# RP2040-Shim-2.net
KiCad netlist of a schematic drawn in EAGLE
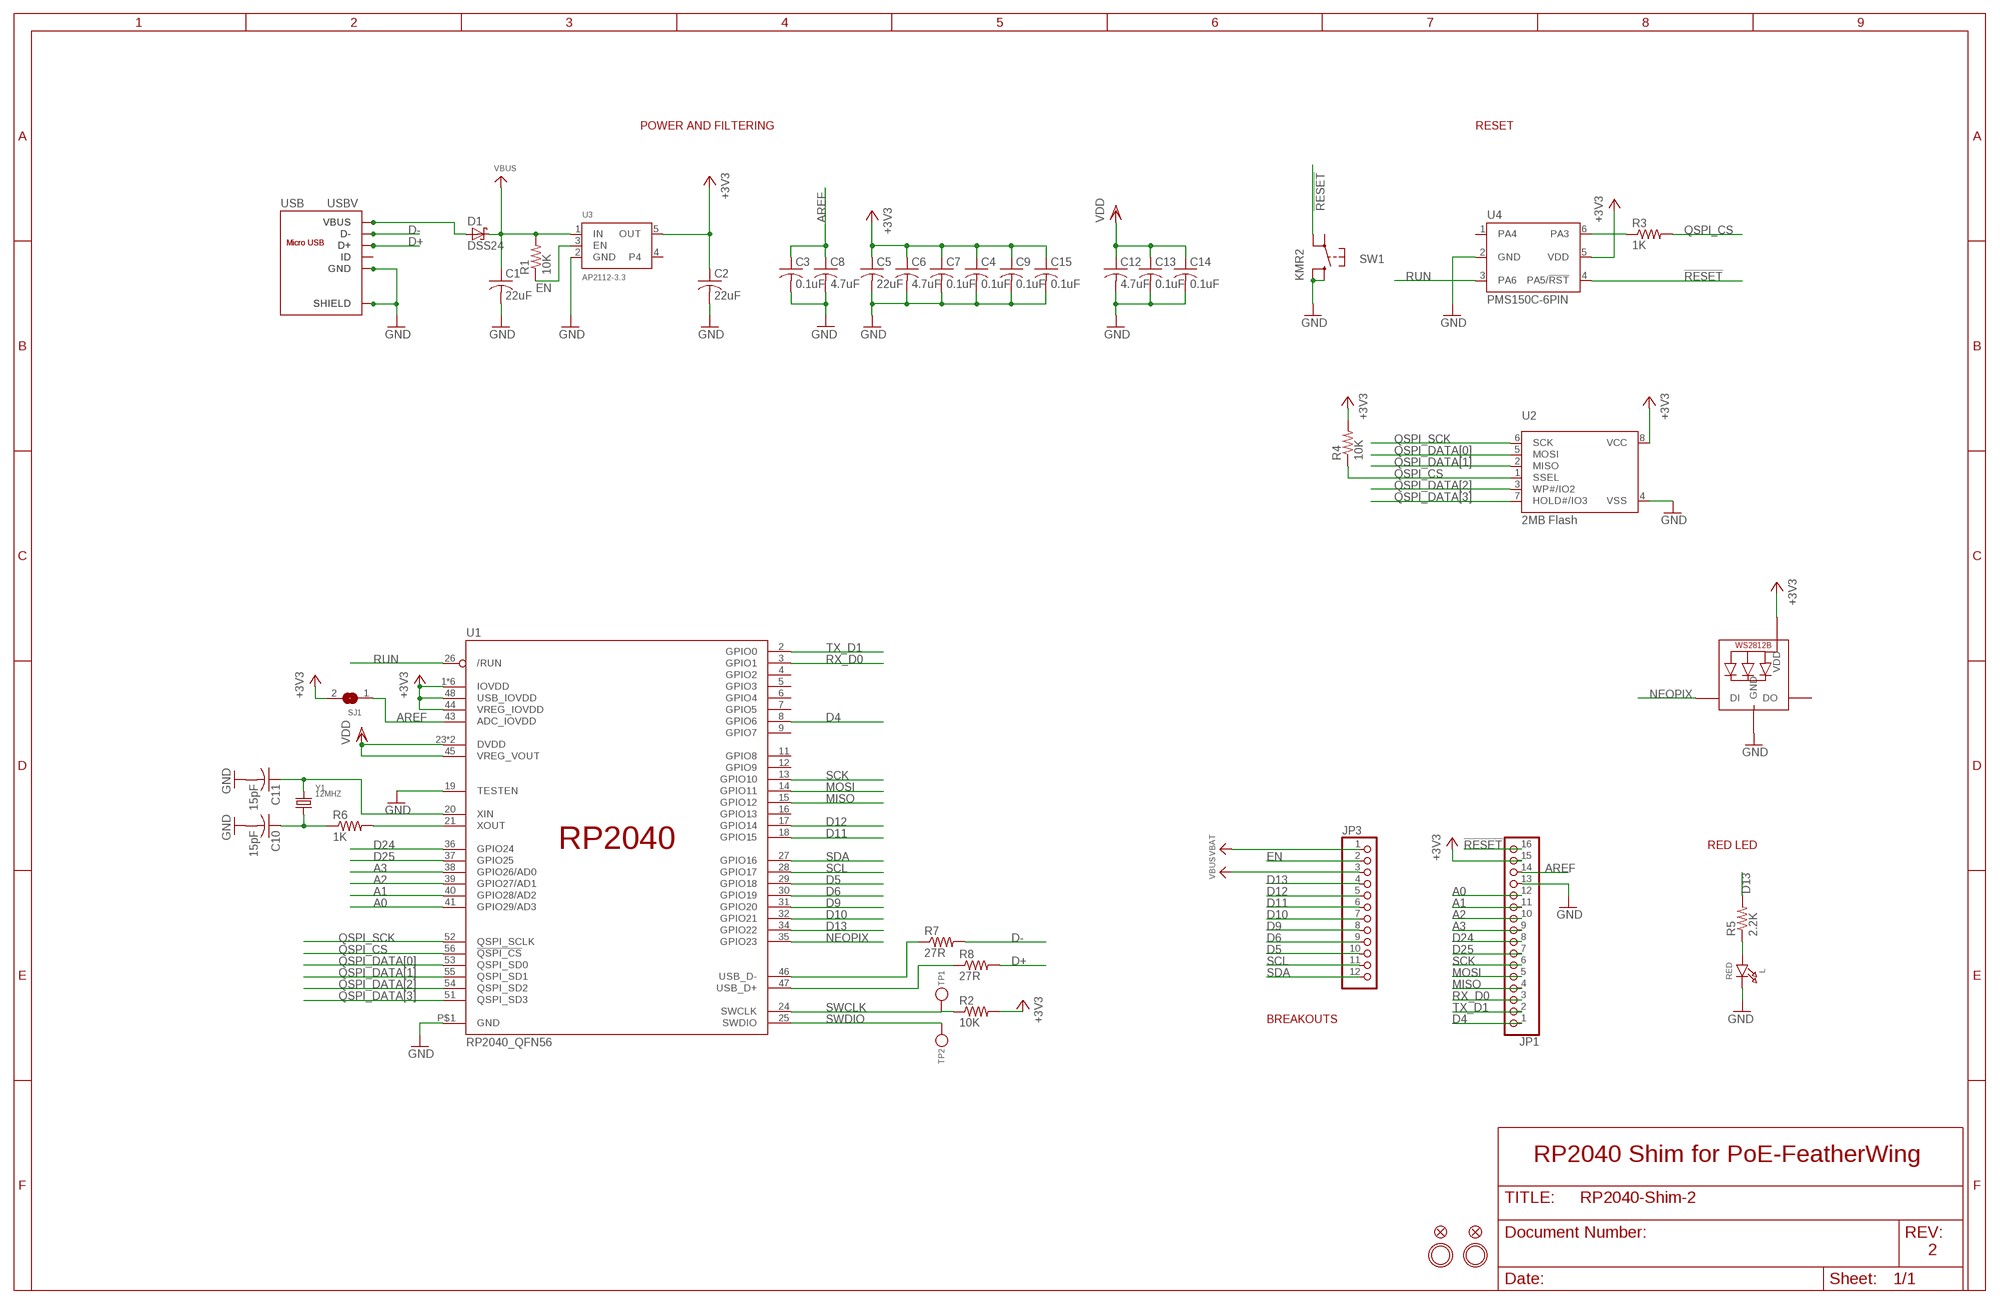
[diagram p0: schematic, sheet 1]

(export (version "E")
  (design (tool "Eeschema 10.0.6"))
  (components
    (comp (ref "C1")
      (value "22uF")
      (footprint "eagle-import:C0805K")
      (libsource (lib "eagle-import") (part "C-USC0805K"))
    )
    (comp (ref "C2")
      (value "22uF")
      (footprint "eagle-import:C0805K")
      (libsource (lib "eagle-import") (part "C-USC0805K"))
    )
    (comp (ref "C3")
      (value "0.1uF")
      (footprint "eagle-import:C0402K")
      (libsource (lib "eagle-import") (part "C-USC0402K"))
    )
    (comp (ref "C4")
      (value "0.1uF")
      (footprint "eagle-import:C0402K")
      (libsource (lib "eagle-import") (part "C-USC0402K"))
    )
    (comp (ref "C5")
      (value "22uF")
      (footprint "eagle-import:C0805K")
      (libsource (lib "eagle-import") (part "C-USC0805K"))
    )
    (comp (ref "C6")
      (value "4.7uF")
      (footprint "eagle-import:C0402K")
      (libsource (lib "eagle-import") (part "C-USC0402K"))
    )
    (comp (ref "C7")
      (value "0.1uF")
      (footprint "eagle-import:C0402K")
      (libsource (lib "eagle-import") (part "C-USC0402K"))
    )
    (comp (ref "C8")
      (value "4.7uF")
      (footprint "eagle-import:C0402K")
      (libsource (lib "eagle-import") (part "C-USC0402K"))
    )
    (comp (ref "C9")
      (value "0.1uF")
      (footprint "eagle-import:C0402K")
      (libsource (lib "eagle-import") (part "C-USC0402K"))
    )
    (comp (ref "C10")
      (value "15pF")
      (footprint "eagle-import:C0402K")
      (libsource (lib "eagle-import") (part "C-USC0402K"))
    )
    (comp (ref "C11")
      (value "15pF")
      (footprint "eagle-import:C0402K")
      (libsource (lib "eagle-import") (part "C-USC0402K"))
    )
    (comp (ref "C12")
      (value "4.7uF")
      (footprint "eagle-import:C0402K")
      (libsource (lib "eagle-import") (part "C-USC0402K"))
    )
    (comp (ref "C13")
      (value "0.1uF")
      (footprint "eagle-import:C0402K")
      (libsource (lib "eagle-import") (part "C-USC0402K"))
    )
    (comp (ref "C14")
      (value "0.1uF")
      (footprint "eagle-import:C0402K")
      (libsource (lib "eagle-import") (part "C-USC0402K"))
    )
    (comp (ref "C15")
      (value "0.1uF")
      (footprint "eagle-import:C0402K")
      (libsource (lib "eagle-import") (part "C-USC0402K"))
    )
    (comp (ref "D1")
      (value "DSS24")
      (footprint "eagle-import:SOD123FL")
      (libsource (lib "eagle-import") (part "DSS24"))
    )
    (comp (ref "JP1")
      (value "HEADER-1X16ROUND")
      (footprint "eagle-import:1X16_ROUND")
      (libsource (lib "eagle-import") (part "HEADER-1X16ROUND"))
    )
    (comp (ref "JP3")
      (value "HEADER-1X12")
      (footprint "eagle-import:1X12_ROUND")
      (libsource (lib "eagle-import") (part "HEADER-1X12"))
    )
    (comp (ref "L")
      (value "RED")
      (footprint "eagle-import:CHIPLED_0805_NOOUTLINE")
      (libsource (lib "eagle-import") (part "LED0805_NOOUTLINE"))
    )
    (comp (ref "LED1")
      (value "WS2812B3535")
      (footprint "eagle-import:LED3535")
      (libsource (lib "eagle-import") (part "WS2812B3535"))
    )
    (comp (ref "R1")
      (value "10K")
      (footprint "eagle-import:R0402")
      (libsource (lib "eagle-import") (part "R-US_R0402"))
    )
    (comp (ref "R2")
      (value "10K")
      (footprint "eagle-import:R0402")
      (libsource (lib "eagle-import") (part "R-US_R0402"))
    )
    (comp (ref "R3")
      (value "1K")
      (footprint "eagle-import:R0402")
      (libsource (lib "eagle-import") (part "R-US_R0402"))
    )
    (comp (ref "R4")
      (value "10K")
      (footprint "eagle-import:R0402")
      (libsource (lib "eagle-import") (part "R-US_R0402"))
    )
    (comp (ref "R5")
      (value "2.2K")
      (footprint "eagle-import:R0402")
      (libsource (lib "eagle-import") (part "R-US_R0402"))
    )
    (comp (ref "R6")
      (value "1K")
      (footprint "eagle-import:R0402")
      (libsource (lib "eagle-import") (part "R-US_R0402"))
    )
    (comp (ref "R7")
      (value "27R")
      (footprint "eagle-import:R0402")
      (libsource (lib "eagle-import") (part "R-US_R0402"))
    )
    (comp (ref "R8")
      (value "27R")
      (footprint "eagle-import:R0402")
      (libsource (lib "eagle-import") (part "R-US_R0402"))
    )
    (comp (ref "SJ1")
      (value "SOLDERJUMPERCLOSED")
      (footprint "eagle-import:SOLDERJUMPER_CLOSEDWIRE")
      (libsource (lib "eagle-import") (part "SOLDERJUMPERCLOSED"))
    )
    (comp (ref "SW1")
      (value "KMR2")
      (footprint "eagle-import:BTN_KMR2_4.6X2.8")
      (libsource (lib "eagle-import") (part "SWITCH_TACT_SMT4.6X2.8"))
    )
    (comp (ref "TP1")
      (value "TESTPOINTROUND1.5MM")
      (footprint "eagle-import:TESTPOINT_ROUND_1.5MM")
      (libsource (lib "eagle-import") (part "TESTPOINTROUND1.5MM"))
    )
    (comp (ref "TP2")
      (value "TESTPOINTROUND1.5MM")
      (footprint "eagle-import:TESTPOINT_ROUND_1.5MM")
      (libsource (lib "eagle-import") (part "TESTPOINTROUND1.5MM"))
    )
    (comp (ref "U$31")
      (value "MOUNTINGHOLE2.5")
      (footprint "eagle-import:MOUNTINGHOLE_2.5_PLATED")
      (libsource (lib "eagle-import") (part "MOUNTINGHOLE2.5"))
    )
    (comp (ref "U$32")
      (value "MOUNTINGHOLE2.5")
      (footprint "eagle-import:MOUNTINGHOLE_2.5_PLATED")
      (libsource (lib "eagle-import") (part "MOUNTINGHOLE2.5"))
    )
    (comp (ref "U$34")
      (value "FIDUCIAL_1MM")
      (footprint "eagle-import:FIDUCIAL_1MM")
      (libsource (lib "eagle-import") (part "FIDUCIAL_1MM"))
    )
    (comp (ref "U$35")
      (value "FIDUCIAL_1MM")
      (footprint "eagle-import:FIDUCIAL_1MM")
      (libsource (lib "eagle-import") (part "FIDUCIAL_1MM"))
    )
    (comp (ref "U1")
      (value "RP2040_QFN56")
      (footprint "eagle-import:QFN56_7MM_REDUCEDEPAD")
      (libsource (lib "eagle-import") (part "RP2040_QFN56"))
    )
    (comp (ref "U2")
      (value "2MB Flash")
      (footprint "eagle-import:USON8")
      (libsource (lib "eagle-import") (part "SPIFLASH_8PINUX"))
    )
    (comp (ref "U3")
      (value "AP2112-3.3")
      (footprint "eagle-import:SOT23-5")
      (libsource (lib "eagle-import") (part "VREG_SOT23-5"))
    )
    (comp (ref "U4")
      (value "PMS150C-6PIN")
      (footprint "eagle-import:SOT23-6")
      (libsource (lib "eagle-import") (part "PMS150C-6PIN"))
    )
    (comp (ref "USB")
      (value "ZX62-B-5PA")
      (footprint "eagle-import:TS-1012E-AC03516")
      (libsource (lib "eagle-import") (part "MICRO-USB-SMD"))
    )
    (comp (ref "USBV")
      (value "MICRO-USB-SMD-VERT")
      (footprint "eagle-import:U-D-M5DS-W-4")
      (libsource (lib "eagle-import") (part "MICRO-USB-SMD-VERT"))
    )
    (comp (ref "Y1")
      (value "12MHZ")
      (footprint "eagle-import:CRYSTAL_2.5X2")
      (libsource (lib "eagle-import") (part "CRYSTAL2.5X2.0"))
    )
  )
  (nets
    (net (code "1") (name "+3V3") (class "Default")
      (node (ref "C15") (pin "1") (pinfunction "1_1") (pintype "passive"))
      (node (ref "C2") (pin "1") (pinfunction "1_1") (pintype "passive"))
      (node (ref "C4") (pin "1") (pinfunction "1_1") (pintype "passive"))
      (node (ref "C5") (pin "1") (pinfunction "1_1") (pintype "passive"))
      (node (ref "C6") (pin "1") (pinfunction "1_1") (pintype "passive"))
      (node (ref "C7") (pin "1") (pinfunction "1_1") (pintype "passive"))
      (node (ref "C9") (pin "1") (pinfunction "1_1") (pintype "passive"))
      (node (ref "JP1") (pin "15") (pinfunction "15_15") (pintype "passive"))
      (node (ref "LED1") (pin "2") (pinfunction "VDD_2") (pintype "power_in"))
      (node (ref "R2") (pin "2") (pinfunction "2_2") (pintype "passive"))
      (node (ref "R4") (pin "2") (pinfunction "2_2") (pintype "passive"))
      (node (ref "SJ1") (pin "2") (pinfunction "2_2") (pintype "passive"))
      (node (ref "U1") (pin "1") (pinfunction "IOVDD_1") (pintype "power_in"))
      (node (ref "U1") (pin "10") (pinfunction "IOVDD_10") (pintype "power_in"))
      (node (ref "U1") (pin "22") (pinfunction "IOVDD_22") (pintype "power_in"))
      (node (ref "U1") (pin "33") (pinfunction "IOVDD_33") (pintype "power_in"))
      (node (ref "U1") (pin "42") (pinfunction "IOVDD_42") (pintype "power_in"))
      (node (ref "U1") (pin "44") (pinfunction "VREG_IOVDD_44") (pintype "power_in"))
      (node (ref "U1") (pin "48") (pinfunction "USB_IOVDD_48") (pintype "power_in"))
      (node (ref "U1") (pin "49") (pinfunction "IOVDD_49") (pintype "power_in"))
      (node (ref "U2") (pin "8") (pinfunction "VCC_8") (pintype "bidirectional"))
      (node (ref "U3") (pin "5") (pinfunction "OUT_5") (pintype "power_in"))
      (node (ref "U4") (pin "5") (pinfunction "VDD_5") (pintype "bidirectional"))
    )
    (net (code "2") (name "/A0") (class "Default")
      (node (ref "JP1") (pin "12") (pinfunction "12_12") (pintype "passive"))
      (node (ref "U1") (pin "41") (pinfunction "GPIO29/AD3_41") (pintype "bidirectional"))
    )
    (net (code "3") (name "/A1") (class "Default")
      (node (ref "JP1") (pin "11") (pinfunction "11_11") (pintype "passive"))
      (node (ref "U1") (pin "40") (pinfunction "GPIO28/AD2_40") (pintype "bidirectional"))
    )
    (net (code "4") (name "/A2") (class "Default")
      (node (ref "JP1") (pin "10") (pinfunction "10_10") (pintype "passive"))
      (node (ref "U1") (pin "39") (pinfunction "GPIO27/AD1_39") (pintype "bidirectional"))
    )
    (net (code "5") (name "/A3") (class "Default")
      (node (ref "JP1") (pin "9") (pinfunction "9_9") (pintype "passive"))
      (node (ref "U1") (pin "38") (pinfunction "GPIO26/AD0_38") (pintype "bidirectional"))
    )
    (net (code "6") (name "/AREF") (class "Default")
      (node (ref "C3") (pin "1") (pinfunction "1_1") (pintype "passive"))
      (node (ref "C8") (pin "1") (pinfunction "1_1") (pintype "passive"))
      (node (ref "JP1") (pin "14") (pinfunction "14_14") (pintype "passive"))
      (node (ref "SJ1") (pin "1") (pinfunction "1_1") (pintype "passive"))
      (node (ref "U1") (pin "43") (pinfunction "ADC_IOVDD_43") (pintype "power_in"))
    )
    (net (code "7") (name "/D+") (class "Default")
      (node (ref "R8") (pin "2") (pinfunction "2_2") (pintype "passive"))
      (node (ref "USB") (pin "3") (pinfunction "D+_3") (pintype "bidirectional"))
      (node (ref "USBV") (pin "3") (pinfunction "D+_3") (pintype "bidirectional"))
    )
    (net (code "8") (name "/D-") (class "Default")
      (node (ref "R7") (pin "2") (pinfunction "2_2") (pintype "passive"))
      (node (ref "USB") (pin "2") (pinfunction "D-_2") (pintype "bidirectional"))
      (node (ref "USBV") (pin "2") (pinfunction "D-_2") (pintype "bidirectional"))
    )
    (net (code "9") (name "/D4") (class "Default")
      (node (ref "JP1") (pin "1") (pinfunction "1_1") (pintype "passive"))
      (node (ref "U1") (pin "8") (pinfunction "GPIO6_8") (pintype "bidirectional"))
    )
    (net (code "10") (name "/D5") (class "Default")
      (node (ref "JP3") (pin "10") (pinfunction "10_10") (pintype "passive"))
      (node (ref "U1") (pin "29") (pinfunction "GPIO18_29") (pintype "bidirectional"))
    )
    (net (code "11") (name "/D6") (class "Default")
      (node (ref "JP3") (pin "9") (pinfunction "9_9") (pintype "passive"))
      (node (ref "U1") (pin "30") (pinfunction "GPIO19_30") (pintype "bidirectional"))
    )
    (net (code "12") (name "/D9") (class "Default")
      (node (ref "JP3") (pin "8") (pinfunction "8_8") (pintype "passive"))
      (node (ref "U1") (pin "31") (pinfunction "GPIO20_31") (pintype "bidirectional"))
    )
    (net (code "13") (name "/D10") (class "Default")
      (node (ref "JP3") (pin "7") (pinfunction "7_7") (pintype "passive"))
      (node (ref "U1") (pin "32") (pinfunction "GPIO21_32") (pintype "bidirectional"))
    )
    (net (code "14") (name "/D11") (class "Default")
      (node (ref "JP3") (pin "6") (pinfunction "6_6") (pintype "passive"))
      (node (ref "U1") (pin "18") (pinfunction "GPIO15_18") (pintype "bidirectional"))
    )
    (net (code "15") (name "/D12") (class "Default")
      (node (ref "JP3") (pin "5") (pinfunction "5_5") (pintype "passive"))
      (node (ref "U1") (pin "17") (pinfunction "GPIO14_17") (pintype "bidirectional"))
    )
    (net (code "16") (name "/D13") (class "Default")
      (node (ref "JP3") (pin "4") (pinfunction "4_4") (pintype "passive"))
      (node (ref "R5") (pin "2") (pinfunction "2_2") (pintype "passive"))
      (node (ref "U1") (pin "34") (pinfunction "GPIO22_34") (pintype "bidirectional"))
    )
    (net (code "17") (name "/D24") (class "Default")
      (node (ref "JP1") (pin "8") (pinfunction "8_8") (pintype "passive"))
      (node (ref "U1") (pin "36") (pinfunction "GPIO24_36") (pintype "bidirectional"))
    )
    (net (code "18") (name "/D25") (class "Default")
      (node (ref "JP1") (pin "7") (pinfunction "7_7") (pintype "passive"))
      (node (ref "U1") (pin "37") (pinfunction "GPIO25_37") (pintype "bidirectional"))
    )
    (net (code "19") (name "/EN") (class "Default")
      (node (ref "JP3") (pin "2") (pinfunction "2_2") (pintype "passive"))
      (node (ref "R1") (pin "1") (pinfunction "1_1") (pintype "passive"))
      (node (ref "U3") (pin "3") (pinfunction "EN_3") (pintype "input"))
    )
    (net (code "20") (name "/MISO") (class "Default")
      (node (ref "JP1") (pin "4") (pinfunction "4_4") (pintype "passive"))
      (node (ref "U1") (pin "15") (pinfunction "GPIO12_15") (pintype "bidirectional"))
    )
    (net (code "21") (name "/MOSI") (class "Default")
      (node (ref "JP1") (pin "5") (pinfunction "5_5") (pintype "passive"))
      (node (ref "U1") (pin "14") (pinfunction "GPIO11_14") (pintype "bidirectional"))
    )
    (net (code "22") (name "/NEOPIX") (class "Default")
      (node (ref "LED1") (pin "1") (pinfunction "DI_1") (pintype "input"))
      (node (ref "U1") (pin "35") (pinfunction "GPIO23_35") (pintype "bidirectional"))
    )
    (net (code "23") (name "/QSPI_CS") (class "Default")
      (node (ref "R3") (pin "2") (pinfunction "2_2") (pintype "passive"))
      (node (ref "R4") (pin "1") (pinfunction "1_1") (pintype "passive"))
      (node (ref "U1") (pin "56") (pinfunction "~{QSPI_CS}_56") (pintype "bidirectional"))
      (node (ref "U2") (pin "1") (pinfunction "SSEL_1") (pintype "bidirectional"))
    )
    (net (code "24") (name "/QSPI_DATA[0]") (class "Default")
      (node (ref "U1") (pin "53") (pinfunction "QSPI_SD0_53") (pintype "bidirectional"))
      (node (ref "U2") (pin "5") (pinfunction "MOSI_5") (pintype "bidirectional"))
    )
    (net (code "25") (name "/QSPI_DATA[1]") (class "Default")
      (node (ref "U1") (pin "55") (pinfunction "QSPI_SD1_55") (pintype "bidirectional"))
      (node (ref "U2") (pin "2") (pinfunction "MISO_2") (pintype "bidirectional"))
    )
    (net (code "26") (name "/QSPI_DATA[2]") (class "Default")
      (node (ref "U1") (pin "54") (pinfunction "QSPI_SD2_54") (pintype "bidirectional"))
      (node (ref "U2") (pin "3") (pinfunction "WP#/IO2_3") (pintype "bidirectional"))
    )
    (net (code "27") (name "/QSPI_DATA[3]") (class "Default")
      (node (ref "U1") (pin "51") (pinfunction "QSPI_SD3_51") (pintype "bidirectional"))
      (node (ref "U2") (pin "7") (pinfunction "HOLD#/IO3_7") (pintype "bidirectional"))
    )
    (net (code "28") (name "/QSPI_SCK") (class "Default")
      (node (ref "U1") (pin "52") (pinfunction "QSPI_SCLK_52") (pintype "bidirectional"))
      (node (ref "U2") (pin "6") (pinfunction "SCK_6") (pintype "bidirectional"))
    )
    (net (code "29") (name "/RUN") (class "Default")
      (node (ref "U1") (pin "26") (pinfunction "/RUN_26") (pintype "bidirectional"))
      (node (ref "U4") (pin "3") (pinfunction "PA6_3") (pintype "bidirectional"))
    )
    (net (code "30") (name "/RX_D0") (class "Default")
      (node (ref "JP1") (pin "3") (pinfunction "3_3") (pintype "passive"))
      (node (ref "U1") (pin "3") (pinfunction "GPIO1_3") (pintype "bidirectional"))
    )
    (net (code "31") (name "/SCK") (class "Default")
      (node (ref "JP1") (pin "6") (pinfunction "6_6") (pintype "passive"))
      (node (ref "U1") (pin "13") (pinfunction "GPIO10_13") (pintype "bidirectional"))
    )
    (net (code "32") (name "/SCL") (class "Default")
      (node (ref "JP3") (pin "11") (pinfunction "11_11") (pintype "passive"))
      (node (ref "U1") (pin "28") (pinfunction "GPIO17_28") (pintype "bidirectional"))
    )
    (net (code "33") (name "/SDA") (class "Default")
      (node (ref "JP3") (pin "12") (pinfunction "12_12") (pintype "passive"))
      (node (ref "U1") (pin "27") (pinfunction "GPIO16_27") (pintype "bidirectional"))
    )
    (net (code "34") (name "/SWCLK") (class "Default")
      (node (ref "R2") (pin "1") (pinfunction "1_1") (pintype "passive"))
      (node (ref "TP1") (pin "P$1") (pinfunction "P$1_P$1") (pintype "bidirectional"))
      (node (ref "U1") (pin "24") (pinfunction "SWCLK_24") (pintype "bidirectional"))
    )
    (net (code "35") (name "/SWDIO") (class "Default")
      (node (ref "TP2") (pin "P$1") (pinfunction "P$1_P$1") (pintype "bidirectional"))
      (node (ref "U1") (pin "25") (pinfunction "SWDIO_25") (pintype "bidirectional"))
    )
    (net (code "36") (name "/TX_D1") (class "Default")
      (node (ref "JP1") (pin "2") (pinfunction "2_2") (pintype "passive"))
      (node (ref "U1") (pin "2") (pinfunction "GPIO0_2") (pintype "bidirectional"))
    )
    (net (code "37") (name "/~{RESET}") (class "Default")
      (node (ref "JP1") (pin "16") (pinfunction "16_16") (pintype "passive"))
      (node (ref "SW1") (pin "A'") (pinfunction "P1_A'") (pintype "passive"))
      (node (ref "U4") (pin "4") (pinfunction "PA5/~{RST}_4") (pintype "bidirectional"))
    )
    (net (code "38") (name "GND") (class "Default")
      (node (ref "C1") (pin "2") (pinfunction "2_2") (pintype "passive"))
      (node (ref "C10") (pin "2") (pinfunction "2_2") (pintype "passive"))
      (node (ref "C11") (pin "2") (pinfunction "2_2") (pintype "passive"))
      (node (ref "C12") (pin "2") (pinfunction "2_2") (pintype "passive"))
      (node (ref "C13") (pin "2") (pinfunction "2_2") (pintype "passive"))
      (node (ref "C14") (pin "2") (pinfunction "2_2") (pintype "passive"))
      (node (ref "C15") (pin "2") (pinfunction "2_2") (pintype "passive"))
      (node (ref "C2") (pin "2") (pinfunction "2_2") (pintype "passive"))
      (node (ref "C3") (pin "2") (pinfunction "2_2") (pintype "passive"))
      (node (ref "C4") (pin "2") (pinfunction "2_2") (pintype "passive"))
      (node (ref "C5") (pin "2") (pinfunction "2_2") (pintype "passive"))
      (node (ref "C6") (pin "2") (pinfunction "2_2") (pintype "passive"))
      (node (ref "C7") (pin "2") (pinfunction "2_2") (pintype "passive"))
      (node (ref "C8") (pin "2") (pinfunction "2_2") (pintype "passive"))
      (node (ref "C9") (pin "2") (pinfunction "2_2") (pintype "passive"))
      (node (ref "JP1") (pin "13") (pinfunction "13_13") (pintype "passive"))
      (node (ref "L") (pin "C") (pinfunction "C_C") (pintype "passive"))
      (node (ref "LED1") (pin "4") (pinfunction "GND_4") (pintype "power_in"))
      (node (ref "SW1") (pin "B") (pinfunction "S_B") (pintype "passive"))
      (node (ref "SW1") (pin "B'") (pinfunction "S1_B'") (pintype "passive"))
      (node (ref "U1") (pin "19") (pinfunction "TESTEN_19") (pintype "input"))
      (node (ref "U1") (pin "P$1") (pinfunction "GND_P$1") (pintype "power_in"))
      (node (ref "U2") (pin "4") (pinfunction "VSS_4") (pintype "bidirectional"))
      (node (ref "U3") (pin "2") (pinfunction "GND_2") (pintype "power_in"))
      (node (ref "U4") (pin "2") (pinfunction "GND_2") (pintype "bidirectional"))
      (node (ref "USB") (pin "5") (pinfunction "GND_5") (pintype "power_in"))
      (node (ref "USB") (pin "P1") (pinfunction "SHIELD_P1") (pintype "power_in"))
      (node (ref "USB") (pin "P2") (pinfunction "SHIELD_P2") (pintype "power_in"))
      (node (ref "USB") (pin "P3") (pinfunction "SHIELD_P3") (pintype "power_in"))
      (node (ref "USB") (pin "P4") (pinfunction "SHIELD_P4") (pintype "power_in"))
      (node (ref "USB") (pin "P5") (pinfunction "SHIELD_P5") (pintype "power_in"))
      (node (ref "USB") (pin "P6") (pinfunction "SHIELD_P6") (pintype "power_in"))
      (node (ref "USBV") (pin "5") (pinfunction "GND_5") (pintype "power_in"))
      (node (ref "USBV") (pin "MNT1") (pinfunction "SHIELD_MNT1") (pintype "power_in"))
      (node (ref "USBV") (pin "MNT2") (pinfunction "SHIELD_MNT2") (pintype "power_in"))
      (node (ref "USBV") (pin "MNT3") (pinfunction "SHIELD_MNT3") (pintype "power_in"))
      (node (ref "USBV") (pin "MNT4") (pinfunction "SHIELD_MNT4") (pintype "power_in"))
    )
    (net (code "39") (name "Net-(C10-Pad1)") (class "Default")
      (node (ref "C10") (pin "1") (pinfunction "1_1") (pintype "passive"))
      (node (ref "R6") (pin "1") (pinfunction "1_1") (pintype "passive"))
      (node (ref "Y1") (pin "1") (pinfunction "1_1") (pintype "passive"))
    )
    (net (code "40") (name "Net-(L-PadA)") (class "Default")
      (node (ref "L") (pin "A") (pinfunction "A_A") (pintype "passive"))
      (node (ref "R5") (pin "1") (pinfunction "1_1") (pintype "passive"))
    )
    (net (code "41") (name "Net-(U1-USB_D+)") (class "Default")
      (node (ref "R8") (pin "1") (pinfunction "1_1") (pintype "passive"))
      (node (ref "U1") (pin "47") (pinfunction "USB_D+_47") (pintype "bidirectional"))
    )
    (net (code "42") (name "Net-(U1-USB_D-)") (class "Default")
      (node (ref "R7") (pin "1") (pinfunction "1_1") (pintype "passive"))
      (node (ref "U1") (pin "46") (pinfunction "USB_D-_46") (pintype "bidirectional"))
    )
    (net (code "43") (name "Net-(U1-XIN)") (class "Default")
      (node (ref "C11") (pin "1") (pinfunction "1_1") (pintype "passive"))
      (node (ref "U1") (pin "20") (pinfunction "XIN_20") (pintype "input"))
      (node (ref "Y1") (pin "3") (pinfunction "2_3") (pintype "passive"))
    )
    (net (code "44") (name "Net-(U1-XOUT)") (class "Default")
      (node (ref "R6") (pin "2") (pinfunction "2_2") (pintype "passive"))
      (node (ref "U1") (pin "21") (pinfunction "XOUT_21") (pintype "output"))
    )
    (net (code "45") (name "Net-(U4-PA3)") (class "Default")
      (node (ref "R3") (pin "1") (pinfunction "1_1") (pintype "passive"))
      (node (ref "U4") (pin "6") (pinfunction "PA3_6") (pintype "bidirectional"))
    )
    (net (code "46") (name "Net-(USB-ID)") (class "Default")
      (node (ref "USB") (pin "4") (pinfunction "ID_4") (pintype "bidirectional"))
      (node (ref "USBV") (pin "4") (pinfunction "ID_4") (pintype "bidirectional"))
    )
    (net (code "47") (name "Net-(USB-VBUS)") (class "Default")
      (node (ref "D1") (pin "A") (pinfunction "A_A") (pintype "passive"))
      (node (ref "USB") (pin "1") (pinfunction "VBUS_1") (pintype "power_in"))
      (node (ref "USBV") (pin "1") (pinfunction "VBUS_1") (pintype "power_in"))
    )
    (net (code "48") (name "VBAT") (class "Default")
      (node (ref "JP3") (pin "1") (pinfunction "1_1") (pintype "passive"))
    )
    (net (code "49") (name "VBUS") (class "Default")
      (node (ref "C1") (pin "1") (pinfunction "1_1") (pintype "passive"))
      (node (ref "D1") (pin "C") (pinfunction "C_C") (pintype "passive"))
      (node (ref "JP3") (pin "3") (pinfunction "3_3") (pintype "passive"))
      (node (ref "R1") (pin "2") (pinfunction "2_2") (pintype "passive"))
      (node (ref "U3") (pin "1") (pinfunction "IN_1") (pintype "power_in"))
    )
    (net (code "50") (name "VDD") (class "Default")
      (node (ref "C12") (pin "1") (pinfunction "1_1") (pintype "passive"))
      (node (ref "C13") (pin "1") (pinfunction "1_1") (pintype "passive"))
      (node (ref "C14") (pin "1") (pinfunction "1_1") (pintype "passive"))
      (node (ref "U1") (pin "23") (pinfunction "DVDD_23") (pintype "power_in"))
      (node (ref "U1") (pin "45") (pinfunction "VREG_VOUT_45") (pintype "power_in"))
      (node (ref "U1") (pin "50") (pinfunction "DVDD_50") (pintype "power_in"))
    )
    (net (code "51") (name "unconnected-(LED1-DO-Pad3)") (class "Default")
      (node (ref "LED1") (pin "3") (pinfunction "DO_3") (pintype "output"))
    )
    (net (code "52") (name "unconnected-(SW1-P-PadA)") (class "Default")
      (node (ref "SW1") (pin "A") (pinfunction "P_A") (pintype "passive"))
    )
    (net (code "53") (name "unconnected-(U1-GPIO2-Pad4)") (class "Default")
      (node (ref "U1") (pin "4") (pinfunction "GPIO2_4") (pintype "bidirectional"))
    )
    (net (code "54") (name "unconnected-(U1-GPIO3-Pad5)") (class "Default")
      (node (ref "U1") (pin "5") (pinfunction "GPIO3_5") (pintype "bidirectional"))
    )
    (net (code "55") (name "unconnected-(U1-GPIO4-Pad6)") (class "Default")
      (node (ref "U1") (pin "6") (pinfunction "GPIO4_6") (pintype "bidirectional"))
    )
    (net (code "56") (name "unconnected-(U1-GPIO5-Pad7)") (class "Default")
      (node (ref "U1") (pin "7") (pinfunction "GPIO5_7") (pintype "bidirectional"))
    )
    (net (code "57") (name "unconnected-(U1-GPIO7-Pad9)") (class "Default")
      (node (ref "U1") (pin "9") (pinfunction "GPIO7_9") (pintype "bidirectional"))
    )
    (net (code "58") (name "unconnected-(U1-GPIO8-Pad11)") (class "Default")
      (node (ref "U1") (pin "11") (pinfunction "GPIO8_11") (pintype "bidirectional"))
    )
    (net (code "59") (name "unconnected-(U1-GPIO9-Pad12)") (class "Default")
      (node (ref "U1") (pin "12") (pinfunction "GPIO9_12") (pintype "bidirectional"))
    )
    (net (code "60") (name "unconnected-(U1-GPIO13-Pad16)") (class "Default")
      (node (ref "U1") (pin "16") (pinfunction "GPIO13_16") (pintype "bidirectional"))
    )
    (net (code "61") (name "unconnected-(U3-P4-Pad4)") (class "Default")
      (node (ref "U3") (pin "4") (pinfunction "P4_4") (pintype "bidirectional"))
    )
    (net (code "62") (name "unconnected-(U4-PA4-Pad1)") (class "Default")
      (node (ref "U4") (pin "1") (pinfunction "PA4_1") (pintype "bidirectional"))
    )
  )
)
